# IoT.net
KiCad netlist of a schematic drawn in EAGLE
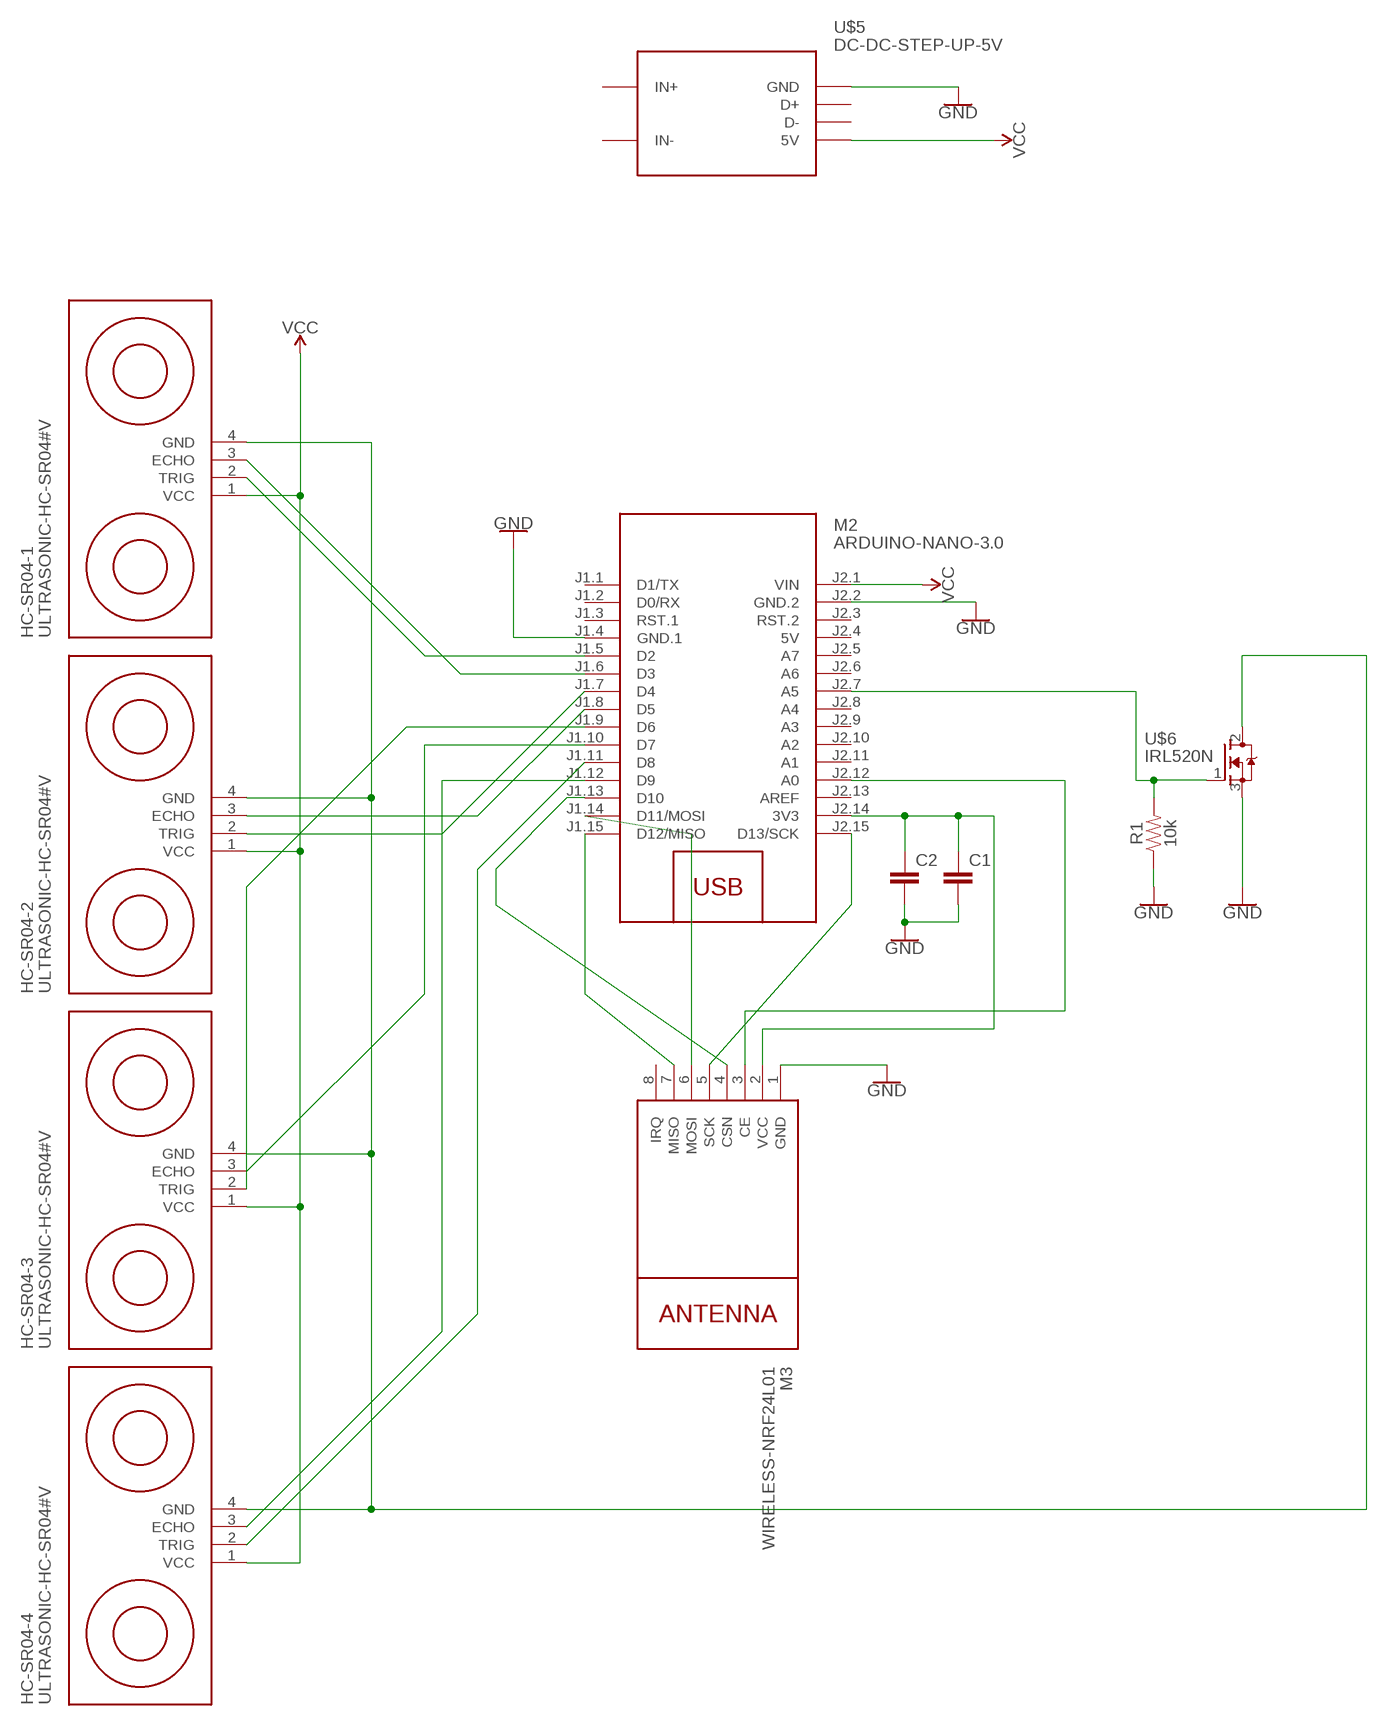
[diagram p0: schematic, sheet 1]

(export (version "E")
  (design (tool "Eeschema 10.0.6"))
  (components
    (comp (ref "C1")
      (value "C-EU025-040X050")
      (footprint "eagle-import:C025-040X050")
      (libsource (lib "eagle-import") (part "C-EU025-040X050"))
    )
    (comp (ref "C2")
      (value "C-EU025-040X050")
      (footprint "eagle-import:C025-040X050")
      (libsource (lib "eagle-import") (part "C-EU025-040X050"))
    )
    (comp (ref "HC-SR04-1")
      (value "ULTRASONIC-HC-SR04#V")
      (footprint "eagle-import:ULTRASONIC-HC-SR04#V")
      (libsource (lib "eagle-import") (part "ULTRASONIC-HC-SR04#V"))
    )
    (comp (ref "HC-SR04-2")
      (value "ULTRASONIC-HC-SR04#V")
      (footprint "eagle-import:ULTRASONIC-HC-SR04#V")
      (libsource (lib "eagle-import") (part "ULTRASONIC-HC-SR04#V"))
    )
    (comp (ref "HC-SR04-3")
      (value "ULTRASONIC-HC-SR04#V")
      (footprint "eagle-import:ULTRASONIC-HC-SR04#V")
      (libsource (lib "eagle-import") (part "ULTRASONIC-HC-SR04#V"))
    )
    (comp (ref "HC-SR04-4")
      (value "ULTRASONIC-HC-SR04#V")
      (footprint "eagle-import:ULTRASONIC-HC-SR04#V")
      (libsource (lib "eagle-import") (part "ULTRASONIC-HC-SR04#V"))
    )
    (comp (ref "M2")
      (value "ARDUINO-NANO-3.0")
      (footprint "eagle-import:ARDUINO-NANO-3.0")
      (libsource (lib "eagle-import") (part "ARDUINO-NANO-3.0"))
    )
    (comp (ref "M3")
      (value "WIRELESS-NRF24L01")
      (footprint "eagle-import:WIRELESS-NRF24L01")
      (libsource (lib "eagle-import") (part "WIRELESS-NRF24L01"))
    )
    (comp (ref "R1")
      (value "10k")
      (footprint "eagle-import:AXIAL-0.3-KIT")
      (libsource (lib "eagle-import") (part "10KOHM-HORIZ_KIT-1/4W-1%"))
    )
    (comp (ref "U$5")
      (value "DC-DC-STEP-UP-5V")
      (footprint "eagle-import:DC-DC-STEP-UP-5V")
      (libsource (lib "eagle-import") (part "DC-DC-STEP-UP-5V"))
    )
    (comp (ref "U$6")
      (value "IRL520N")
      (footprint "eagle-import:TO220-VERT")
      (fields (field (name "MF") "International Rectifier"))
      (libsource (lib "eagle-import") (part "IRL520N"))
    )
  )
  (nets
    (net (code "1") (name "/5V") (class "Default")
      (node (ref "M2") (pin "J2.4") (pinfunction "5V_J2.4") (pintype "power_in"))
    )
    (net (code "2") (name "/IN+") (class "Default")
      (node (ref "U$5") (pin "IN+") (pinfunction "IN+_IN+") (pintype "power_in"))
    )
    (net (code "3") (name "/IN-") (class "Default")
      (node (ref "U$5") (pin "IN-") (pinfunction "IN-_IN-") (pintype "power_in"))
    )
    (net (code "4") (name "GND") (class "Default")
      (node (ref "C1") (pin "2") (pinfunction "2_2") (pintype "passive"))
      (node (ref "C2") (pin "2") (pinfunction "2_2") (pintype "passive"))
      (node (ref "M2") (pin "J1.4") (pinfunction "GND.1_J1.4") (pintype "power_in"))
      (node (ref "M2") (pin "J2.2") (pinfunction "GND.2_J2.2") (pintype "power_in"))
      (node (ref "M3") (pin "1") (pinfunction "GND_1") (pintype "power_in"))
      (node (ref "R1") (pin "P$1") (pinfunction "1_P$1") (pintype "passive"))
      (node (ref "U$5") (pin "GND") (pinfunction "GND_GND") (pintype "bidirectional"))
      (node (ref "U$6") (pin "3") (pinfunction "S_3") (pintype "power_in"))
    )
    (net (code "5") (name "Net-(HC-SR04-1-ECHO)") (class "Default")
      (node (ref "HC-SR04-1") (pin "3") (pinfunction "ECHO_3") (pintype "output"))
      (node (ref "M2") (pin "J1.6") (pinfunction "D3_J1.6") (pintype "bidirectional"))
    )
    (net (code "6") (name "Net-(HC-SR04-1-GND)") (class "Default")
      (node (ref "HC-SR04-1") (pin "4") (pinfunction "GND_4") (pintype "power_in"))
      (node (ref "HC-SR04-2") (pin "4") (pinfunction "GND_4") (pintype "power_in"))
      (node (ref "HC-SR04-3") (pin "4") (pinfunction "GND_4") (pintype "power_in"))
      (node (ref "HC-SR04-4") (pin "4") (pinfunction "GND_4") (pintype "power_in"))
      (node (ref "U$6") (pin "2") (pinfunction "D_2") (pintype "power_in"))
    )
    (net (code "7") (name "Net-(HC-SR04-1-TRIG)") (class "Default")
      (node (ref "HC-SR04-1") (pin "2") (pinfunction "TRIG_2") (pintype "input"))
      (node (ref "M2") (pin "J1.5") (pinfunction "D2_J1.5") (pintype "bidirectional"))
    )
    (net (code "8") (name "Net-(HC-SR04-2-ECHO)") (class "Default")
      (node (ref "HC-SR04-2") (pin "3") (pinfunction "ECHO_3") (pintype "output"))
      (node (ref "M2") (pin "J1.8") (pinfunction "D5_J1.8") (pintype "bidirectional"))
    )
    (net (code "9") (name "Net-(HC-SR04-2-TRIG)") (class "Default")
      (node (ref "HC-SR04-2") (pin "2") (pinfunction "TRIG_2") (pintype "input"))
      (node (ref "M2") (pin "J1.7") (pinfunction "D4_J1.7") (pintype "bidirectional"))
    )
    (net (code "10") (name "Net-(HC-SR04-3-ECHO)") (class "Default")
      (node (ref "HC-SR04-3") (pin "3") (pinfunction "ECHO_3") (pintype "output"))
      (node (ref "M2") (pin "J1.10") (pinfunction "D7_J1.10") (pintype "bidirectional"))
    )
    (net (code "11") (name "Net-(HC-SR04-3-TRIG)") (class "Default")
      (node (ref "HC-SR04-3") (pin "2") (pinfunction "TRIG_2") (pintype "input"))
      (node (ref "M2") (pin "J1.9") (pinfunction "D6_J1.9") (pintype "bidirectional"))
    )
    (net (code "12") (name "Net-(HC-SR04-4-ECHO)") (class "Default")
      (node (ref "HC-SR04-4") (pin "3") (pinfunction "ECHO_3") (pintype "output"))
      (node (ref "M2") (pin "J1.12") (pinfunction "D9_J1.12") (pintype "bidirectional"))
    )
    (net (code "13") (name "Net-(HC-SR04-4-TRIG)") (class "Default")
      (node (ref "HC-SR04-4") (pin "2") (pinfunction "TRIG_2") (pintype "input"))
      (node (ref "M2") (pin "J1.11") (pinfunction "D8_J1.11") (pintype "bidirectional"))
    )
    (net (code "14") (name "Net-(M2-3V3)") (class "Default")
      (node (ref "C1") (pin "1") (pinfunction "1_1") (pintype "passive"))
      (node (ref "C2") (pin "1") (pinfunction "1_1") (pintype "passive"))
      (node (ref "M2") (pin "J2.14") (pinfunction "3V3_J2.14") (pintype "power_in"))
      (node (ref "M3") (pin "2") (pinfunction "VCC_2") (pintype "power_in"))
    )
    (net (code "15") (name "Net-(M2-A0)") (class "Default")
      (node (ref "M2") (pin "J2.12") (pinfunction "A0_J2.12") (pintype "bidirectional"))
      (node (ref "M3") (pin "3") (pinfunction "CE_3") (pintype "bidirectional"))
    )
    (net (code "16") (name "Net-(M2-A5)") (class "Default")
      (node (ref "M2") (pin "J2.7") (pinfunction "A5_J2.7") (pintype "bidirectional"))
      (node (ref "R1") (pin "P$2") (pinfunction "2_P$2") (pintype "passive"))
      (node (ref "U$6") (pin "1") (pinfunction "G_1") (pintype "power_in"))
    )
    (net (code "17") (name "Net-(M2-D10)") (class "Default")
      (node (ref "M2") (pin "J1.13") (pinfunction "D10_J1.13") (pintype "bidirectional"))
      (node (ref "M3") (pin "4") (pinfunction "CSN_4") (pintype "bidirectional"))
    )
    (net (code "18") (name "Net-(M2-D11{slash}MOSI)") (class "Default")
      (node (ref "M2") (pin "J1.14") (pinfunction "D11/MOSI_J1.14") (pintype "bidirectional"))
      (node (ref "M3") (pin "6") (pinfunction "MOSI_6") (pintype "bidirectional"))
    )
    (net (code "19") (name "Net-(M2-D12{slash}MISO)") (class "Default")
      (node (ref "M2") (pin "J1.15") (pinfunction "D12/MISO_J1.15") (pintype "bidirectional"))
      (node (ref "M3") (pin "7") (pinfunction "MISO_7") (pintype "bidirectional"))
    )
    (net (code "20") (name "Net-(M2-D13{slash}SCK)") (class "Default")
      (node (ref "M2") (pin "J2.15") (pinfunction "D13/SCK_J2.15") (pintype "bidirectional"))
      (node (ref "M3") (pin "5") (pinfunction "SCK_5") (pintype "bidirectional"))
    )
    (net (code "21") (name "VCC") (class "Default")
      (node (ref "HC-SR04-1") (pin "1") (pinfunction "VCC_1") (pintype "power_in"))
      (node (ref "HC-SR04-2") (pin "1") (pinfunction "VCC_1") (pintype "power_in"))
      (node (ref "HC-SR04-3") (pin "1") (pinfunction "VCC_1") (pintype "power_in"))
      (node (ref "HC-SR04-4") (pin "1") (pinfunction "VCC_1") (pintype "power_in"))
      (node (ref "M2") (pin "J2.1") (pinfunction "VIN_J2.1") (pintype "power_in"))
      (node (ref "U$5") (pin "5V") (pinfunction "5V_5V") (pintype "bidirectional"))
    )
    (net (code "22") (name "unconnected-(M2-A1-PadJ2.11)") (class "Default")
      (node (ref "M2") (pin "J2.11") (pinfunction "A1_J2.11") (pintype "bidirectional"))
    )
    (net (code "23") (name "unconnected-(M2-A2-PadJ2.10)") (class "Default")
      (node (ref "M2") (pin "J2.10") (pinfunction "A2_J2.10") (pintype "bidirectional"))
    )
    (net (code "24") (name "unconnected-(M2-A3-PadJ2.9)") (class "Default")
      (node (ref "M2") (pin "J2.9") (pinfunction "A3_J2.9") (pintype "bidirectional"))
    )
    (net (code "25") (name "unconnected-(M2-A4-PadJ2.8)") (class "Default")
      (node (ref "M2") (pin "J2.8") (pinfunction "A4_J2.8") (pintype "bidirectional"))
    )
    (net (code "26") (name "unconnected-(M2-A6-PadJ2.6)") (class "Default")
      (node (ref "M2") (pin "J2.6") (pinfunction "A6_J2.6") (pintype "bidirectional"))
    )
    (net (code "27") (name "unconnected-(M2-A7-PadJ2.5)") (class "Default")
      (node (ref "M2") (pin "J2.5") (pinfunction "A7_J2.5") (pintype "bidirectional"))
    )
    (net (code "28") (name "unconnected-(M2-AREF-PadJ2.13)") (class "Default")
      (node (ref "M2") (pin "J2.13") (pinfunction "AREF_J2.13") (pintype "bidirectional"))
    )
    (net (code "29") (name "unconnected-(M2-D0{slash}RX-PadJ1.2)") (class "Default")
      (node (ref "M2") (pin "J1.2") (pinfunction "D0/RX_J1.2") (pintype "bidirectional"))
    )
    (net (code "30") (name "unconnected-(M2-D1{slash}TX-PadJ1.1)") (class "Default")
      (node (ref "M2") (pin "J1.1") (pinfunction "D1/TX_J1.1") (pintype "bidirectional"))
    )
    (net (code "31") (name "unconnected-(M2-RST.1-PadJ1.3)") (class "Default")
      (node (ref "M2") (pin "J1.3") (pinfunction "RST.1_J1.3") (pintype "bidirectional"))
    )
    (net (code "32") (name "unconnected-(M2-RST.2-PadJ2.3)") (class "Default")
      (node (ref "M2") (pin "J2.3") (pinfunction "RST.2_J2.3") (pintype "bidirectional"))
    )
    (net (code "33") (name "unconnected-(M3-IRQ-Pad8)") (class "Default")
      (node (ref "M3") (pin "8") (pinfunction "IRQ_8") (pintype "bidirectional"))
    )
    (net (code "34") (name "unconnected-(U$5-PadD+)") (class "Default")
      (node (ref "U$5") (pin "D+") (pinfunction "D+_D+") (pintype "bidirectional"))
    )
    (net (code "35") (name "unconnected-(U$5-PadD-)") (class "Default")
      (node (ref "U$5") (pin "D-") (pinfunction "D-_D-") (pintype "bidirectional"))
    )
  )
)
